# nrf52withamp.net
KiCad netlist of a schematic drawn in EAGLE
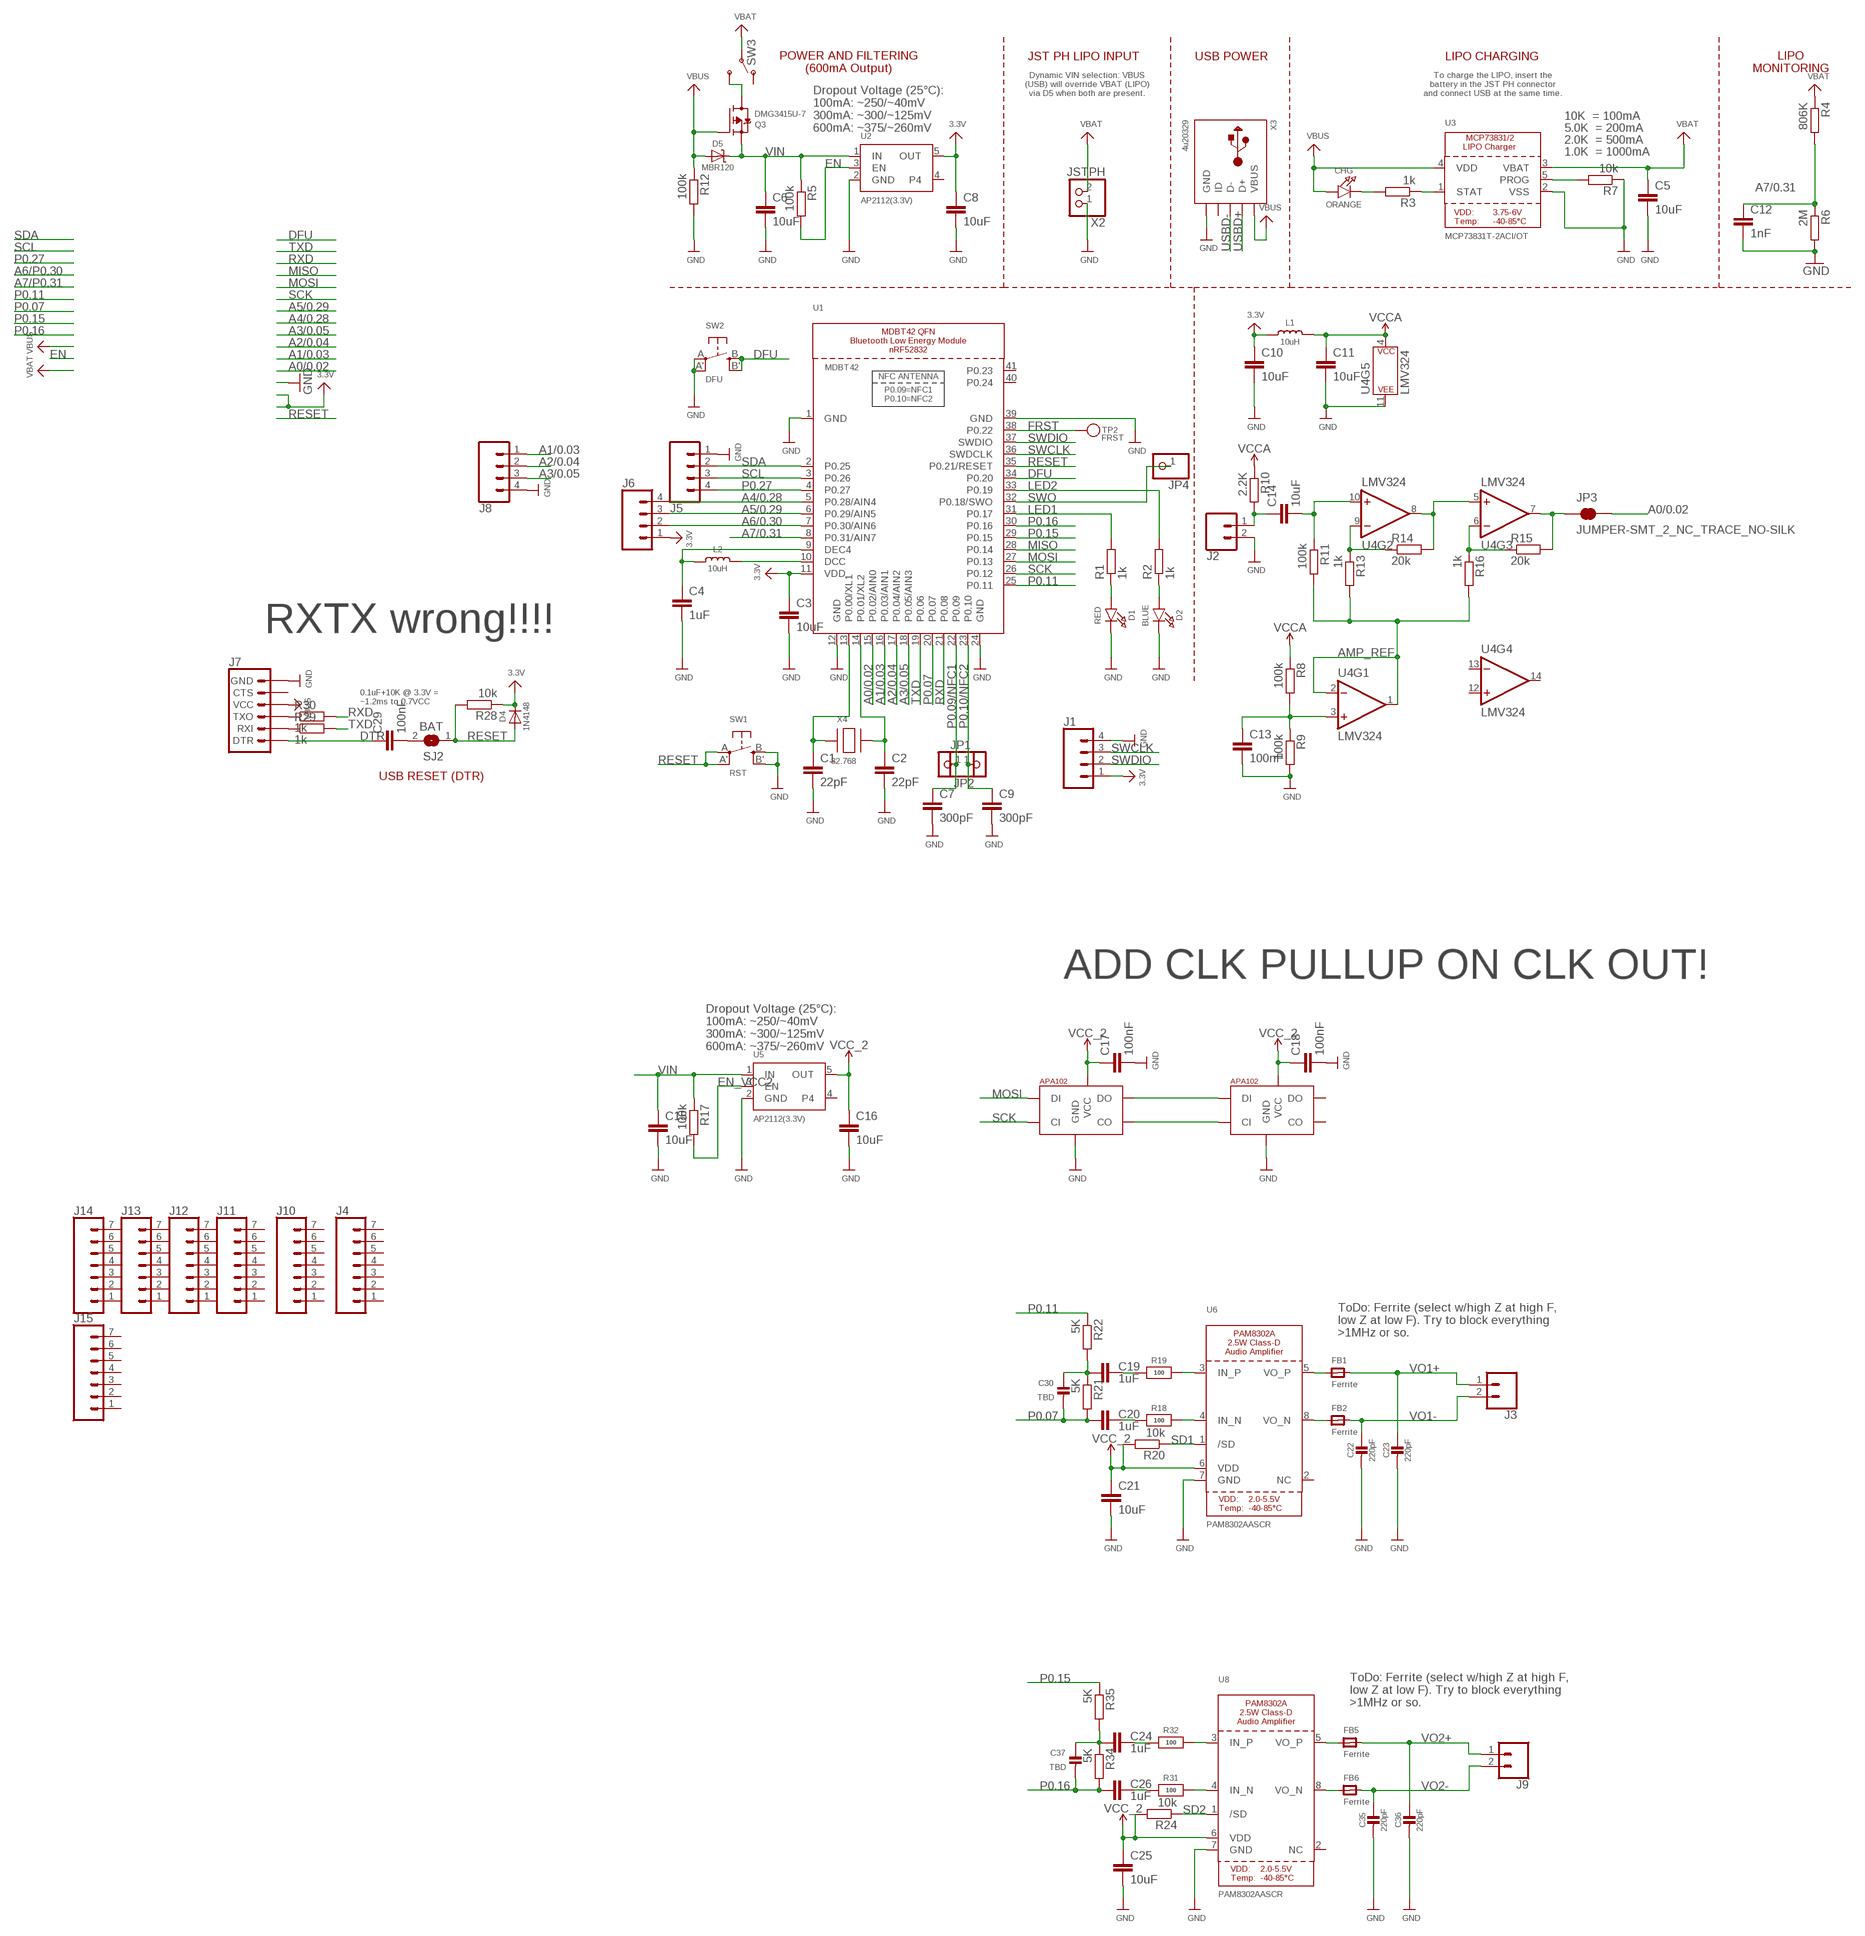
[diagram p0: schematic, sheet 1]

(export (version "E")
  (design (tool "Eeschema 10.0.6"))
  (components
    (comp (ref "C1")
      (value "22pF")
      (footprint "eagle-import:C0805")
      (libsource (lib "eagle-import") (part "C-EUC0805"))
    )
    (comp (ref "C2")
      (value "22pF")
      (footprint "eagle-import:C0805")
      (libsource (lib "eagle-import") (part "C-EUC0805"))
    )
    (comp (ref "C3")
      (value "10uF")
      (footprint "eagle-import:C0805")
      (libsource (lib "eagle-import") (part "C-EUC0805"))
    )
    (comp (ref "C4")
      (value "1uF")
      (footprint "eagle-import:C0805")
      (libsource (lib "eagle-import") (part "C-EUC0805"))
    )
    (comp (ref "C5")
      (value "10uF")
      (footprint "eagle-import:C0805")
      (libsource (lib "eagle-import") (part "C-EUC0805"))
    )
    (comp (ref "C6")
      (value "10uF")
      (footprint "eagle-import:C0805")
      (libsource (lib "eagle-import") (part "C-EUC0805"))
    )
    (comp (ref "C7")
      (value "300pF")
      (footprint "eagle-import:C0805")
      (libsource (lib "eagle-import") (part "C-EUC0805"))
    )
    (comp (ref "C8")
      (value "10uF")
      (footprint "eagle-import:C0805")
      (libsource (lib "eagle-import") (part "C-EUC0805"))
    )
    (comp (ref "C9")
      (value "300pF")
      (footprint "eagle-import:C0805")
      (libsource (lib "eagle-import") (part "C-EUC0805"))
    )
    (comp (ref "C10")
      (value "10uF")
      (footprint "eagle-import:C0805")
      (libsource (lib "eagle-import") (part "C-EUC0805"))
    )
    (comp (ref "C11")
      (value "10uF")
      (footprint "eagle-import:C0805")
      (libsource (lib "eagle-import") (part "C-EUC0805"))
    )
    (comp (ref "C12")
      (value "1nF")
      (footprint "eagle-import:C0805")
      (libsource (lib "eagle-import") (part "C-EUC0805"))
    )
    (comp (ref "C13")
      (value "100nF")
      (footprint "eagle-import:C0805")
      (libsource (lib "eagle-import") (part "C-EUC0805"))
    )
    (comp (ref "C14")
      (value "10uF")
      (footprint "eagle-import:C0805")
      (libsource (lib "eagle-import") (part "C-EUC0805"))
    )
    (comp (ref "C15")
      (value "10uF")
      (footprint "eagle-import:C0805")
      (libsource (lib "eagle-import") (part "C-EUC0805"))
    )
    (comp (ref "C16")
      (value "10uF")
      (footprint "eagle-import:C0805")
      (libsource (lib "eagle-import") (part "C-EUC0805"))
    )
    (comp (ref "C17")
      (value "100nF")
      (footprint "eagle-import:C0805")
      (libsource (lib "eagle-import") (part "C-EUC0805"))
    )
    (comp (ref "C18")
      (value "100nF")
      (footprint "eagle-import:C0805")
      (libsource (lib "eagle-import") (part "C-EUC0805"))
    )
    (comp (ref "C19")
      (value "1uF")
      (footprint "eagle-import:C0805")
      (libsource (lib "eagle-import") (part "C-EUC0805"))
    )
    (comp (ref "C20")
      (value "1uF")
      (footprint "eagle-import:C0805")
      (libsource (lib "eagle-import") (part "C-EUC0805"))
    )
    (comp (ref "C21")
      (value "10uF")
      (footprint "eagle-import:C0805")
      (libsource (lib "eagle-import") (part "C-EUC0805"))
    )
    (comp (ref "C22")
      (value "220pF")
      (footprint "eagle-import:0805-NO")
      (libsource (lib "eagle-import") (part "CAP_CERAMIC0805-NOOUTLINE"))
    )
    (comp (ref "C23")
      (value "220pF")
      (footprint "eagle-import:0805-NO")
      (libsource (lib "eagle-import") (part "CAP_CERAMIC0805-NOOUTLINE"))
    )
    (comp (ref "C24")
      (value "1uF")
      (footprint "eagle-import:C0805")
      (libsource (lib "eagle-import") (part "C-EUC0805"))
    )
    (comp (ref "C25")
      (value "10uF")
      (footprint "eagle-import:C0805")
      (libsource (lib "eagle-import") (part "C-EUC0805"))
    )
    (comp (ref "C26")
      (value "1uF")
      (footprint "eagle-import:C0805")
      (libsource (lib "eagle-import") (part "C-EUC0805"))
    )
    (comp (ref "C29")
      (value "100nF")
      (footprint "eagle-import:C0805")
      (libsource (lib "eagle-import") (part "C-EUC0805"))
    )
    (comp (ref "C30")
      (value "TBD")
      (footprint "eagle-import:0805-NO")
      (libsource (lib "eagle-import") (part "CAP_CERAMIC0805-NOOUTLINE"))
    )
    (comp (ref "C35")
      (value "220pF")
      (footprint "eagle-import:0805-NO")
      (libsource (lib "eagle-import") (part "CAP_CERAMIC0805-NOOUTLINE"))
    )
    (comp (ref "C36")
      (value "220pF")
      (footprint "eagle-import:0805-NO")
      (libsource (lib "eagle-import") (part "CAP_CERAMIC0805-NOOUTLINE"))
    )
    (comp (ref "C37")
      (value "TBD")
      (footprint "eagle-import:0805-NO")
      (libsource (lib "eagle-import") (part "CAP_CERAMIC0805-NOOUTLINE"))
    )
    (comp (ref "CHG")
      (value "ORANGE")
      (footprint "eagle-import:CHIPLED_0805_NOOUTLINE")
      (libsource (lib "eagle-import") (part "LED0805_NOOUTLINE"))
    )
    (comp (ref "D1")
      (value "RED")
      (footprint "eagle-import:CHIPLED_0805_NOOUTLINE")
      (libsource (lib "eagle-import") (part "LED0805_NOOUTLINE"))
    )
    (comp (ref "D2")
      (value "BLUE")
      (footprint "eagle-import:CHIPLED_0805_NOOUTLINE")
      (libsource (lib "eagle-import") (part "LED0805_NOOUTLINE"))
    )
    (comp (ref "D4")
      (value "1N4148")
      (footprint "eagle-import:SOD-323")
      (libsource (lib "eagle-import") (part "DIODESOD-323"))
    )
    (comp (ref "D5")
      (value "MBR120")
      (footprint "eagle-import:SOD-123")
      (libsource (lib "eagle-import") (part "DIODE-SCHOTTKYSOD-123"))
    )
    (comp (ref "FB1")
      (value "Ferrite")
      (footprint "eagle-import:_0805")
      (libsource (lib "eagle-import") (part "FERRITE_0805"))
    )
    (comp (ref "FB2")
      (value "Ferrite")
      (footprint "eagle-import:_0805")
      (libsource (lib "eagle-import") (part "FERRITE_0805"))
    )
    (comp (ref "FB5")
      (value "Ferrite")
      (footprint "eagle-import:_0805")
      (libsource (lib "eagle-import") (part "FERRITE_0805"))
    )
    (comp (ref "FB6")
      (value "Ferrite")
      (footprint "eagle-import:_0805")
      (libsource (lib "eagle-import") (part "FERRITE_0805"))
    )
    (comp (ref "J1")
      (value "CONN_04SMD")
      (footprint "eagle-import:1X04_SMD_RA_MALE")
      (libsource (lib "eagle-import") (part "CONN_04SMD"))
    )
    (comp (ref "J2")
      (value "CONN_02")
      (footprint "eagle-import:1X02")
      (libsource (lib "eagle-import") (part "CONN_02"))
    )
    (comp (ref "J3")
      (value "CONN_02")
      (footprint "eagle-import:1X02")
      (libsource (lib "eagle-import") (part "CONN_02"))
    )
    (comp (ref "J4")
      (value "CONN_07")
      (footprint "eagle-import:1X07")
      (libsource (lib "eagle-import") (part "CONN_07"))
    )
    (comp (ref "J5")
      (value "CONN_041.27MM")
      (footprint "eagle-import:1X04_1.27MM")
      (libsource (lib "eagle-import") (part "CONN_041.27MM"))
    )
    (comp (ref "J6")
      (value "CONN_041.27MM")
      (footprint "eagle-import:1X04_1.27MM")
      (libsource (lib "eagle-import") (part "CONN_041.27MM"))
    )
    (comp (ref "J7")
      (value "6_PIN_SERIAL_TARGETRA_SMT")
      (footprint "eagle-import:6_PIN_SERIAL_TARGET_SIDE_RA_SMT")
      (libsource (lib "eagle-import") (part "6_PIN_SERIAL_TARGETRA_SMT"))
    )
    (comp (ref "J8")
      (value "CONN_041.27MM")
      (footprint "eagle-import:1X04_1.27MM")
      (libsource (lib "eagle-import") (part "CONN_041.27MM"))
    )
    (comp (ref "J9")
      (value "CONN_02")
      (footprint "eagle-import:1X02")
      (libsource (lib "eagle-import") (part "CONN_02"))
    )
    (comp (ref "J10")
      (value "CONN_07")
      (footprint "eagle-import:1X07")
      (libsource (lib "eagle-import") (part "CONN_07"))
    )
    (comp (ref "J11")
      (value "CONN_07")
      (footprint "eagle-import:1X07")
      (libsource (lib "eagle-import") (part "CONN_07"))
    )
    (comp (ref "J12")
      (value "CONN_07")
      (footprint "eagle-import:1X07")
      (libsource (lib "eagle-import") (part "CONN_07"))
    )
    (comp (ref "J13")
      (value "CONN_07")
      (footprint "eagle-import:1X07")
      (libsource (lib "eagle-import") (part "CONN_07"))
    )
    (comp (ref "J14")
      (value "CONN_07")
      (footprint "eagle-import:1X07")
      (libsource (lib "eagle-import") (part "CONN_07"))
    )
    (comp (ref "J15")
      (value "CONN_07")
      (footprint "eagle-import:1X07")
      (libsource (lib "eagle-import") (part "CONN_07"))
    )
    (comp (ref "JP1")
      (value "HEADER-1X12MM")
      (footprint "eagle-import:1X01_2MM")
      (libsource (lib "eagle-import") (part "HEADER-1X12MM"))
    )
    (comp (ref "JP2")
      (value "HEADER-1X12MM")
      (footprint "eagle-import:1X01_2MM")
      (libsource (lib "eagle-import") (part "HEADER-1X12MM"))
    )
    (comp (ref "JP3")
      (value "JUMPER-SMT_2_NC_TRACE_NO-SILK")
      (footprint "eagle-import:SMT-JUMPER_2_NC_TRACE_NO-SILK")
      (libsource (lib "eagle-import") (part "JUMPER-SMT_2_NC_TRACE_NO-SILK"))
    )
    (comp (ref "JP4")
      (value "HEADER-1X12MM")
      (footprint "eagle-import:1X01_2MM")
      (libsource (lib "eagle-import") (part "HEADER-1X12MM"))
    )
    (comp (ref "L1")
      (value "10uH")
      (footprint "eagle-import:0805-NO@1")
      (libsource (lib "eagle-import") (part "INDUCTOR0805-NO"))
    )
    (comp (ref "L2")
      (value "10uH")
      (footprint "eagle-import:0805-NO@1")
      (libsource (lib "eagle-import") (part "INDUCTOR0805-NO"))
    )
    (comp (ref "Q3")
      (value "DMG3415U-7")
      (footprint "eagle-import:SOT23-R")
      (libsource (lib "eagle-import") (part "MOSFET-P"))
    )
    (comp (ref "R1")
      (value "1k")
      (footprint "eagle-import:R0805")
      (libsource (lib "eagle-import") (part "R-EU_R0805"))
    )
    (comp (ref "R2")
      (value "1k")
      (footprint "eagle-import:R0805")
      (libsource (lib "eagle-import") (part "R-EU_R0805"))
    )
    (comp (ref "R3")
      (value "1k")
      (footprint "eagle-import:R0805")
      (libsource (lib "eagle-import") (part "R-EU_R0805"))
    )
    (comp (ref "R4")
      (value "806K")
      (footprint "eagle-import:R0805")
      (libsource (lib "eagle-import") (part "R-EU_R0805"))
    )
    (comp (ref "R5")
      (value "100k")
      (footprint "eagle-import:R0805")
      (libsource (lib "eagle-import") (part "R-EU_R0805"))
    )
    (comp (ref "R6")
      (value "2M")
      (footprint "eagle-import:R0805")
      (libsource (lib "eagle-import") (part "R-EU_R0805"))
    )
    (comp (ref "R7")
      (value "10k")
      (footprint "eagle-import:R0805")
      (libsource (lib "eagle-import") (part "R-EU_R0805"))
    )
    (comp (ref "R8")
      (value "100k")
      (footprint "eagle-import:R0805")
      (libsource (lib "eagle-import") (part "R-EU_R0805"))
    )
    (comp (ref "R9")
      (value "100k")
      (footprint "eagle-import:R0805")
      (libsource (lib "eagle-import") (part "R-EU_R0805"))
    )
    (comp (ref "R10")
      (value "2.2K")
      (footprint "eagle-import:R0805")
      (libsource (lib "eagle-import") (part "R-EU_R0805"))
    )
    (comp (ref "R11")
      (value "100k")
      (footprint "eagle-import:R0805")
      (libsource (lib "eagle-import") (part "R-EU_R0805"))
    )
    (comp (ref "R12")
      (value "100k")
      (footprint "eagle-import:R0805")
      (libsource (lib "eagle-import") (part "R-EU_R0805"))
    )
    (comp (ref "R13")
      (value "1k")
      (footprint "eagle-import:R0805")
      (libsource (lib "eagle-import") (part "R-EU_R0805"))
    )
    (comp (ref "R14")
      (value "20k")
      (footprint "eagle-import:R0805")
      (libsource (lib "eagle-import") (part "R-EU_R0805"))
    )
    (comp (ref "R15")
      (value "20k")
      (footprint "eagle-import:R0805")
      (libsource (lib "eagle-import") (part "R-EU_R0805"))
    )
    (comp (ref "R16")
      (value "1k")
      (footprint "eagle-import:R0805")
      (libsource (lib "eagle-import") (part "R-EU_R0805"))
    )
    (comp (ref "R17")
      (value "100k")
      (footprint "eagle-import:R0805")
      (libsource (lib "eagle-import") (part "R-EU_R0805"))
    )
    (comp (ref "R18")
      (value "100")
      (footprint "eagle-import:0805-NO")
      (libsource (lib "eagle-import") (part "RESISTOR0805_NOOUTLINE"))
    )
    (comp (ref "R19")
      (value "100")
      (footprint "eagle-import:0805-NO")
      (libsource (lib "eagle-import") (part "RESISTOR0805_NOOUTLINE"))
    )
    (comp (ref "R20")
      (value "10k")
      (footprint "eagle-import:R0805")
      (libsource (lib "eagle-import") (part "R-EU_R0805"))
    )
    (comp (ref "R21")
      (value "5K")
      (footprint "eagle-import:R0805")
      (libsource (lib "eagle-import") (part "R-EU_R0805"))
    )
    (comp (ref "R22")
      (value "5K")
      (footprint "eagle-import:R0805")
      (libsource (lib "eagle-import") (part "R-EU_R0805"))
    )
    (comp (ref "R24")
      (value "10k")
      (footprint "eagle-import:R0805")
      (libsource (lib "eagle-import") (part "R-EU_R0805"))
    )
    (comp (ref "R28")
      (value "10k")
      (footprint "eagle-import:R0805")
      (libsource (lib "eagle-import") (part "R-EU_R0805"))
    )
    (comp (ref "R29")
      (value "1k")
      (footprint "eagle-import:R0805")
      (libsource (lib "eagle-import") (part "R-EU_R0805"))
    )
    (comp (ref "R30")
      (value "1k")
      (footprint "eagle-import:R0805")
      (libsource (lib "eagle-import") (part "R-EU_R0805"))
    )
    (comp (ref "R31")
      (value "100")
      (footprint "eagle-import:0805-NO")
      (libsource (lib "eagle-import") (part "RESISTOR0805_NOOUTLINE"))
    )
    (comp (ref "R32")
      (value "100")
      (footprint "eagle-import:0805-NO")
      (libsource (lib "eagle-import") (part "RESISTOR0805_NOOUTLINE"))
    )
    (comp (ref "R34")
      (value "5K")
      (footprint "eagle-import:R0805")
      (libsource (lib "eagle-import") (part "R-EU_R0805"))
    )
    (comp (ref "R35")
      (value "5K")
      (footprint "eagle-import:R0805")
      (libsource (lib "eagle-import") (part "R-EU_R0805"))
    )
    (comp (ref "SJ2")
      (value "BAT")
      (footprint "eagle-import:SOLDERJUMPER_CLOSEDWIRE")
      (libsource (lib "eagle-import") (part "SOLDERJUMPERCLOSED"))
    )
    (comp (ref "SW1")
      (value "RST")
      (footprint "eagle-import:BTN_KMR2_4.6X2.8")
      (libsource (lib "eagle-import") (part "SWITCH_TACT_SMT4.6X2.8"))
    )
    (comp (ref "SW2")
      (value "DFU")
      (footprint "eagle-import:BTN_KMR2_4.6X2.8")
      (libsource (lib "eagle-import") (part "SWITCH_TACT_SMT4.6X2.8"))
    )
    (comp (ref "SW3")
      (value "SWITCH_SPDT")
      (footprint "eagle-import:KPS-1290")
      (libsource (lib "eagle-import") (part "SWITCH_SPDT"))
    )
    (comp (ref "TP2")
      (value "FRST")
      (footprint "eagle-import:PAD-1.5X2.0")
      (libsource (lib "eagle-import") (part "TESTPOINT1.5X2.0MM_NOCREAM"))
    )
    (comp (ref "U$45")
      (value "APA1022020")
      (footprint "eagle-import:APA102_2020")
      (libsource (lib "eagle-import") (part "APA1022020"))
    )
    (comp (ref "U$51")
      (value "APA1022020")
      (footprint "eagle-import:APA102_2020")
      (libsource (lib "eagle-import") (part "APA1022020"))
    )
    (comp (ref "U1")
      (value "MDBT42")
      (footprint "eagle-import:BLE_MODULE_RAYTAC_MDBT42")
      (libsource (lib "eagle-import") (part "NRF52832_MODULE_MDBT42"))
    )
    (comp (ref "U2")
      (value "AP2112(3.3V)")
      (footprint "eagle-import:SOT23-5")
      (libsource (lib "eagle-import") (part "VREG_SOT23-5"))
    )
    (comp (ref "U3")
      (value "MCP73831T-2ACI/OT")
      (footprint "eagle-import:SOT23-5")
      (libsource (lib "eagle-import") (part "MCP73831/2"))
    )
    (comp (ref "U4")
      (value "LMV324")
      (footprint "eagle-import:SO14")
      (fields (field (name "LCSC") "C7974"))
      (libsource (lib "eagle-import") (part "LMV324"))
    )
    (comp (ref "U5")
      (value "AP2112(3.3V)")
      (footprint "eagle-import:SOT23-5")
      (libsource (lib "eagle-import") (part "VREG_SOT23-5"))
    )
    (comp (ref "U6")
      (value "PAM8302AASCR")
      (footprint "eagle-import:MSOP8_0.65MM")
      (libsource (lib "eagle-import") (part "AUDIOAMP_PAM8302A"))
    )
    (comp (ref "U8")
      (value "PAM8302AASCR")
      (footprint "eagle-import:MSOP8_0.65MM")
      (libsource (lib "eagle-import") (part "AUDIOAMP_PAM8302A"))
    )
    (comp (ref "X2")
      (value "JSTPH")
      (footprint "eagle-import:JSTPH2")
      (libsource (lib "eagle-import") (part "CON_JST_PH_2PIN"))
    )
    (comp (ref "X3")
      (value "4u20329")
      (footprint "eagle-import:4UCONN_20329_V2")
      (libsource (lib "eagle-import") (part "USB_MICRO_20329_V2"))
    )
    (comp (ref "X4")
      (value "32.768")
      (footprint "eagle-import:XTAL3215")
      (libsource (lib "eagle-import") (part "XTAL-3.2X1.5"))
    )
  )
  (nets
    (net (code "1") (name "/A0{slash}0.02") (class "Default")
      (node (ref "JP3") (pin "2") (pinfunction "2_2") (pintype "passive"))
      (node (ref "U1") (pin "15") (pinfunction "P0.02/AIN0_15") (pintype "bidirectional"))
    )
    (net (code "2") (name "/A1{slash}0.03") (class "Default")
      (node (ref "J8") (pin "1") (pinfunction "1_1") (pintype "passive"))
      (node (ref "U1") (pin "16") (pinfunction "P0.03/AIN1_16") (pintype "bidirectional"))
    )
    (net (code "3") (name "/A2{slash}0.04") (class "Default")
      (node (ref "J8") (pin "2") (pinfunction "2_2") (pintype "passive"))
      (node (ref "U1") (pin "17") (pinfunction "P0.04/AIN2_17") (pintype "bidirectional"))
    )
    (net (code "4") (name "/A3{slash}0.05") (class "Default")
      (node (ref "J8") (pin "3") (pinfunction "3_3") (pintype "passive"))
      (node (ref "U1") (pin "18") (pinfunction "P0.05/AIN3_18") (pintype "bidirectional"))
    )
    (net (code "5") (name "/A4{slash}0.28") (class "Default")
      (node (ref "J6") (pin "4") (pinfunction "4_4") (pintype "passive"))
      (node (ref "U1") (pin "5") (pinfunction "P0.28/AIN4_5") (pintype "bidirectional"))
    )
    (net (code "6") (name "/A5{slash}0.29") (class "Default")
      (node (ref "J6") (pin "3") (pinfunction "3_3") (pintype "passive"))
      (node (ref "U1") (pin "6") (pinfunction "P0.29/AIN5_6") (pintype "bidirectional"))
    )
    (net (code "7") (name "/A6{slash}0.30") (class "Default")
      (node (ref "J6") (pin "2") (pinfunction "2_2") (pintype "passive"))
      (node (ref "U1") (pin "7") (pinfunction "P0.30/AIN6_7") (pintype "bidirectional"))
    )
    (net (code "9") (name "/A7{slash}0.31") (class "Default")
      (node (ref "C12") (pin "1") (pinfunction "1_1") (pintype "passive"))
      (node (ref "R4") (pin "2") (pinfunction "2_2") (pintype "passive"))
      (node (ref "R6") (pin "1") (pinfunction "1_1") (pintype "passive"))
      (node (ref "U1") (pin "8") (pinfunction "P0.31/AIN7_8") (pintype "bidirectional"))
    )
    (net (code "11") (name "/AMP_REF") (class "Default")
      (node (ref "R11") (pin "2") (pinfunction "2_2") (pintype "passive"))
      (node (ref "R13") (pin "2") (pinfunction "2_2") (pintype "passive"))
      (node (ref "R16") (pin "2") (pinfunction "2_2") (pintype "passive"))
      (node (ref "U4") (pin "1") (pinfunction "OUT_1") (pintype "output"))
      (node (ref "U4") (pin "2") (pinfunction "-IN_2") (pintype "input"))
    )
    (net (code "12") (name "/DFU") (class "Default")
      (node (ref "SW2") (pin "B") (pinfunction "S_B") (pintype "passive"))
      (node (ref "SW2") (pin "B'") (pinfunction "S1_B'") (pintype "passive"))
      (node (ref "U1") (pin "34") (pinfunction "P0.20_34") (pintype "bidirectional"))
    )
    (net (code "13") (name "/DTR") (class "Default")
      (node (ref "C29") (pin "1") (pinfunction "1_1") (pintype "passive"))
      (node (ref "J7") (pin "1") (pinfunction "DTR_1") (pintype "passive"))
    )
    (net (code "14") (name "/EN") (class "Default")
      (node (ref "R5") (pin "2") (pinfunction "2_2") (pintype "passive"))
      (node (ref "U2") (pin "3") (pinfunction "EN_3") (pintype "input"))
    )
    (net (code "15") (name "/EN_VCC2") (class "Default")
      (node (ref "R17") (pin "2") (pinfunction "2_2") (pintype "passive"))
      (node (ref "U5") (pin "3") (pinfunction "EN_3") (pintype "input"))
    )
    (net (code "16") (name "/FRST") (class "Default")
      (node (ref "TP2") (pin "P$1") (pinfunction "P$1_P$1") (pintype "bidirectional"))
      (node (ref "U1") (pin "38") (pinfunction "P0.22_38") (pintype "bidirectional"))
    )
    (net (code "17") (name "/LED1") (class "Default")
      (node (ref "R1") (pin "2") (pinfunction "2_2") (pintype "passive"))
      (node (ref "U1") (pin "31") (pinfunction "P0.17_31") (pintype "bidirectional"))
    )
    (net (code "18") (name "/LED2") (class "Default")
      (node (ref "R2") (pin "2") (pinfunction "2_2") (pintype "passive"))
      (node (ref "U1") (pin "33") (pinfunction "P0.19_33") (pintype "bidirectional"))
    )
    (net (code "19") (name "/MISO") (class "Default")
      (node (ref "U1") (pin "28") (pinfunction "P0.14_28") (pintype "bidirectional"))
    )
    (net (code "20") (name "/MOSI") (class "Default")
      (node (ref "U$45") (pin "D_IN") (pinfunction "DI_D_IN") (pintype "bidirectional"))
      (node (ref "U1") (pin "27") (pinfunction "P0.13_27") (pintype "bidirectional"))
    )
    (net (code "21") (name "/P0.07") (class "Default")
      (node (ref "C20") (pin "1") (pinfunction "1_1") (pintype "passive"))
      (node (ref "C30") (pin "2") (pinfunction "2_2") (pintype "passive"))
      (node (ref "R21") (pin "2") (pinfunction "2_2") (pintype "passive"))
      (node (ref "U1") (pin "20") (pinfunction "P0.07_20") (pintype "bidirectional"))
    )
    (net (code "22") (name "/P0.09{slash}NFC1") (class "Default")
      (node (ref "C7") (pin "1") (pinfunction "1_1") (pintype "passive"))
      (node (ref "JP2") (pin "1") (pinfunction "1_1") (pintype "passive"))
      (node (ref "U1") (pin "22") (pinfunction "P0.09_22") (pintype "bidirectional"))
    )
    (net (code "23") (name "/P0.10{slash}NFC2") (class "Default")
      (node (ref "C9") (pin "1") (pinfunction "1_1") (pintype "passive"))
      (node (ref "JP1") (pin "1") (pinfunction "1_1") (pintype "passive"))
      (node (ref "U1") (pin "23") (pinfunction "P0.10_23") (pintype "bidirectional"))
    )
    (net (code "24") (name "/P0.11") (class "Default")
      (node (ref "R22") (pin "1") (pinfunction "1_1") (pintype "passive"))
      (node (ref "U1") (pin "25") (pinfunction "P0.11_25") (pintype "bidirectional"))
    )
    (net (code "25") (name "/P0.15") (class "Default")
      (node (ref "R35") (pin "1") (pinfunction "1_1") (pintype "passive"))
      (node (ref "U1") (pin "29") (pinfunction "P0.15_29") (pintype "bidirectional"))
    )
    (net (code "26") (name "/P0.16") (class "Default")
      (node (ref "C26") (pin "1") (pinfunction "1_1") (pintype "passive"))
      (node (ref "C37") (pin "2") (pinfunction "2_2") (pintype "passive"))
      (node (ref "R34") (pin "2") (pinfunction "2_2") (pintype "passive"))
      (node (ref "U1") (pin "30") (pinfunction "P0.16_30") (pintype "bidirectional"))
    )
    (net (code "27") (name "/P0.27") (class "Default")
      (node (ref "J5") (pin "4") (pinfunction "4_4") (pintype "passive"))
      (node (ref "U1") (pin "4") (pinfunction "P0.27_4") (pintype "bidirectional"))
    )
    (net (code "28") (name "/RESET") (class "Default")
      (node (ref "D4") (pin "A") (pinfunction "A_A") (pintype "passive"))
      (node (ref "R28") (pin "2") (pinfunction "2_2") (pintype "passive"))
      (node (ref "SJ2") (pin "1") (pinfunction "1_1") (pintype "passive"))
      (node (ref "SW1") (pin "A") (pinfunction "P_A") (pintype "passive"))
      (node (ref "SW1") (pin "A'") (pinfunction "P1_A'") (pintype "passive"))
      (node (ref "U1") (pin "35") (pinfunction "P0.21/RESET_35") (pintype "bidirectional"))
    )
    (net (code "29") (name "/RXD") (class "Default")
      (node (ref "R30") (pin "2") (pinfunction "2_2") (pintype "passive"))
      (node (ref "U1") (pin "21") (pinfunction "P0.08_21") (pintype "bidirectional"))
    )
    (net (code "30") (name "/SCK") (class "Default")
      (node (ref "U$45") (pin "C_IN") (pinfunction "CI_C_IN") (pintype "bidirectional"))
      (node (ref "U1") (pin "26") (pinfunction "P0.12_26") (pintype "bidirectional"))
    )
    (net (code "31") (name "/SCL") (class "Default")
      (node (ref "J5") (pin "3") (pinfunction "3_3") (pintype "passive"))
      (node (ref "U1") (pin "3") (pinfunction "P0.26_3") (pintype "bidirectional"))
    )
    (net (code "32") (name "/SD1") (class "Default")
      (node (ref "R20") (pin "1") (pinfunction "1_1") (pintype "passive"))
      (node (ref "U6") (pin "1") (pinfunction "/SD_1") (pintype "input"))
    )
    (net (code "33") (name "/SD2") (class "Default")
      (node (ref "R24") (pin "1") (pinfunction "1_1") (pintype "passive"))
      (node (ref "U8") (pin "1") (pinfunction "/SD_1") (pintype "input"))
    )
    (net (code "34") (name "/SDA") (class "Default")
      (node (ref "J5") (pin "2") (pinfunction "2_2") (pintype "passive"))
      (node (ref "U1") (pin "2") (pinfunction "P0.25_2") (pintype "bidirectional"))
    )
    (net (code "35") (name "/SWCLK") (class "Default")
      (node (ref "J1") (pin "3") (pinfunction "3_3") (pintype "passive"))
      (node (ref "U1") (pin "36") (pinfunction "SWDCLK_36") (pintype "bidirectional"))
    )
    (net (code "36") (name "/SWDIO") (class "Default")
      (node (ref "J1") (pin "2") (pinfunction "2_2") (pintype "passive"))
      (node (ref "U1") (pin "37") (pinfunction "SWDIO_37") (pintype "bidirectional"))
    )
    (net (code "37") (name "/SWO") (class "Default")
      (node (ref "JP4") (pin "1") (pinfunction "1_1") (pintype "passive"))
      (node (ref "U1") (pin "32") (pinfunction "P0.18/SWO_32") (pintype "bidirectional"))
    )
    (net (code "38") (name "/TXD") (class "Default")
      (node (ref "R29") (pin "2") (pinfunction "2_2") (pintype "passive"))
      (node (ref "U1") (pin "19") (pinfunction "P0.06_19") (pintype "bidirectional"))
    )
    (net (code "39") (name "/USBD+") (class "Default")
      (node (ref "X3") (pin "D+") (pinfunction "D+_D+") (pintype "bidirectional"))
    )
    (net (code "40") (name "/USBD-") (class "Default")
      (node (ref "X3") (pin "D-") (pinfunction "D-_D-") (pintype "bidirectional"))
    )
    (net (code "41") (name "/VIN") (class "Default")
      (node (ref "C15") (pin "1") (pinfunction "1_1") (pintype "passive"))
      (node (ref "C6") (pin "1") (pinfunction "1_1") (pintype "passive"))
      (node (ref "D5") (pin "C") (pinfunction "C_C") (pintype "passive"))
      (node (ref "Q3") (pin "2") (pinfunction "S_2") (pintype "passive"))
      (node (ref "R17") (pin "1") (pinfunction "1_1") (pintype "passive"))
      (node (ref "R5") (pin "1") (pinfunction "1_1") (pintype "passive"))
      (node (ref "U2") (pin "1") (pinfunction "IN_1") (pintype "power_in"))
      (node (ref "U5") (pin "1") (pinfunction "IN_1") (pintype "power_in"))
    )
    (net (code "42") (name "/VO1+") (class "Default")
      (node (ref "C23") (pin "1") (pinfunction "1_1") (pintype "passive"))
      (node (ref "FB1") (pin "2") (pinfunction "P$2_2") (pintype "passive"))
      (node (ref "J3") (pin "1") (pinfunction "1_1") (pintype "passive"))
    )
    (net (code "43") (name "/VO1-") (class "Default")
      (node (ref "C22") (pin "1") (pinfunction "1_1") (pintype "passive"))
      (node (ref "FB2") (pin "2") (pinfunction "P$2_2") (pintype "passive"))
      (node (ref "J3") (pin "2") (pinfunction "2_2") (pintype "passive"))
    )
    (net (code "44") (name "/VO2+") (class "Default")
      (node (ref "C36") (pin "1") (pinfunction "1_1") (pintype "passive"))
      (node (ref "FB5") (pin "2") (pinfunction "P$2_2") (pintype "passive"))
      (node (ref "J9") (pin "1") (pinfunction "1_1") (pintype "passive"))
    )
    (net (code "45") (name "/VO2-") (class "Default")
      (node (ref "C35") (pin "1") (pinfunction "1_1") (pintype "passive"))
      (node (ref "FB6") (pin "2") (pinfunction "P$2_2") (pintype "passive"))
      (node (ref "J9") (pin "2") (pinfunction "2_2") (pintype "passive"))
    )
    (net (code "46") (name "3.3V") (class "Default")
      (node (ref "C10") (pin "1") (pinfunction "1_1") (pintype "passive"))
      (node (ref "C3") (pin "1") (pinfunction "1_1") (pintype "passive"))
      (node (ref "C8") (pin "1") (pinfunction "1_1") (pintype "passive"))
      (node (ref "D4") (pin "C") (pinfunction "C_C") (pintype "passive"))
      (node (ref "J1") (pin "1") (pinfunction "1_1") (pintype "passive"))
      (node (ref "J6") (pin "1") (pinfunction "1_1") (pintype "passive"))
      (node (ref "L1") (pin "1") (pinfunction "1_1") (pintype "passive"))
      (node (ref "R28") (pin "1") (pinfunction "1_1") (pintype "passive"))
      (node (ref "U1") (pin "11") (pinfunction "VDD_11") (pintype "bidirectional"))
      (node (ref "U2") (pin "5") (pinfunction "OUT_5") (pintype "power_in"))
    )
    (net (code "47") (name "GND") (class "Default")
      (node (ref "C1") (pin "2") (pinfunction "2_2") (pintype "passive"))
      (node (ref "C10") (pin "2") (pinfunction "2_2") (pintype "passive"))
      (node (ref "C11") (pin "2") (pinfunction "2_2") (pintype "passive"))
      (node (ref "C12") (pin "2") (pinfunction "2_2") (pintype "passive"))
      (node (ref "C13") (pin "2") (pinfunction "2_2") (pintype "passive"))
      (node (ref "C15") (pin "2") (pinfunction "2_2") (pintype "passive"))
      (node (ref "C16") (pin "2") (pinfunction "2_2") (pintype "passive"))
      (node (ref "C17") (pin "2") (pinfunction "2_2") (pintype "passive"))
      (node (ref "C18") (pin "2") (pinfunction "2_2") (pintype "passive"))
      (node (ref "C2") (pin "2") (pinfunction "2_2") (pintype "passive"))
      (node (ref "C21") (pin "2") (pinfunction "2_2") (pintype "passive"))
      (node (ref "C22") (pin "2") (pinfunction "2_2") (pintype "passive"))
      (node (ref "C23") (pin "2") (pinfunction "2_2") (pintype "passive"))
      (node (ref "C25") (pin "2") (pinfunction "2_2") (pintype "passive"))
      (node (ref "C3") (pin "2") (pinfunction "2_2") (pintype "passive"))
      (node (ref "C35") (pin "2") (pinfunction "2_2") (pintype "passive"))
      (node (ref "C36") (pin "2") (pinfunction "2_2") (pintype "passive"))
      (node (ref "C4") (pin "2") (pinfunction "2_2") (pintype "passive"))
      (node (ref "C5") (pin "2") (pinfunction "2_2") (pintype "passive"))
      (node (ref "C6") (pin "2") (pinfunction "2_2") (pintype "passive"))
      (node (ref "C7") (pin "2") (pinfunction "2_2") (pintype "passive"))
      (node (ref "C8") (pin "2") (pinfunction "2_2") (pintype "passive"))
      (node (ref "C9") (pin "2") (pinfunction "2_2") (pintype "passive"))
      (node (ref "D1") (pin "C") (pinfunction "C_C") (pintype "passive"))
      (node (ref "D2") (pin "C") (pinfunction "C_C") (pintype "passive"))
      (node (ref "J1") (pin "4") (pinfunction "4_4") (pintype "passive"))
      (node (ref "J2") (pin "2") (pinfunction "2_2") (pintype "passive"))
      (node (ref "J5") (pin "1") (pinfunction "1_1") (pintype "passive"))
      (node (ref "J7") (pin "6") (pinfunction "GND_6") (pintype "passive"))
      (node (ref "J8") (pin "4") (pinfunction "4_4") (pintype "passive"))
      (node (ref "R12") (pin "2") (pinfunction "2_2") (pintype "passive"))
      (node (ref "R6") (pin "2") (pinfunction "2_2") (pintype "passive"))
      (node (ref "R7") (pin "1") (pinfunction "1_1") (pintype "passive"))
      (node (ref "R9") (pin "2") (pinfunction "2_2") (pintype "passive"))
      (node (ref "SW1") (pin "B") (pinfunction "S_B") (pintype "passive"))
      (node (ref "SW1") (pin "B'") (pinfunction "S1_B'") (pintype "passive"))
      (node (ref "SW2") (pin "A") (pinfunction "P_A") (pintype "passive"))
      (node (ref "SW2") (pin "A'") (pinfunction "P1_A'") (pintype "passive"))
      (node (ref "U$45") (pin "GND") (pinfunction "GND_GND") (pintype "bidirectional"))
      (node (ref "U$51") (pin "GND") (pinfunction "GND_GND") (pintype "bidirectional"))
      (node (ref "U1") (pin "1") (pinfunction "GND_1") (pintype "bidirectional"))
      (node (ref "U1") (pin "12") (pinfunction "GND_12") (pintype "bidirectional"))
      (node (ref "U1") (pin "24") (pinfunction "GND_24") (pintype "bidirectional"))
      (node (ref "U1") (pin "39") (pinfunction "GND_39") (pintype "bidirectional"))
      (node (ref "U2") (pin "2") (pinfunction "GND_2") (pintype "power_in"))
      (node (ref "U3") (pin "2") (pinfunction "VSS_2") (pintype "power_in"))
      (node (ref "U4") (pin "11") (pinfunction "P$V-_11") (pintype "bidirectional"))
      (node (ref "U5") (pin "2") (pinfunction "GND_2") (pintype "power_in"))
      (node (ref "U6") (pin "7") (pinfunction "GND_7") (pintype "power_in"))
      (node (ref "U8") (pin "7") (pinfunction "GND_7") (pintype "power_in"))
      (node (ref "X2") (pin "1") (pinfunction "1_1") (pintype "passive"))
      (node (ref "X3") (pin "BASE@1") (pinfunction "GND_BASE@1") (pintype "power_in"))
      (node (ref "X3") (pin "BASE@2") (pinfunction "GND_BASE@2") (pintype "power_in"))
      (node (ref "X3") (pin "GND") (pinfunction "GND_GND") (pintype "power_in"))
      (node (ref "X3") (pin "SPRT@1") (pinfunction "GND_SPRT@1") (pintype "power_in"))
      (node (ref "X3") (pin "SPRT@2") (pinfunction "GND_SPRT@2") (pintype "power_in"))
      (node (ref "X3") (pin "SPRT@3") (pinfunction "GND_SPRT@3") (pintype "power_in"))
      (node (ref "X3") (pin "SPRT@4") (pinfunction "GND_SPRT@4") (pintype "power_in"))
    )
    (net (code "48") (name "Net-(C14-Pad1)") (class "Default")
      (node (ref "C14") (pin "1") (pinfunction "1_1") (pintype "passive"))
      (node (ref "J2") (pin "1") (pinfunction "1_1") (pintype "passive"))
      (node (ref "R10") (pin "2") (pinfunction "2_2") (pintype "passive"))
    )
    (net (code "49") (name "Net-(C19-Pad1)") (class "Default")
      (node (ref "C19") (pin "1") (pinfunction "1_1") (pintype "passive"))
      (node (ref "C30") (pin "1") (pinfunction "1_1") (pintype "passive"))
      (node (ref "R21") (pin "1") (pinfunction "1_1") (pintype "passive"))
      (node (ref "R22") (pin "2") (pinfunction "2_2") (pintype "passive"))
    )
    (net (code "50") (name "Net-(C19-Pad2)") (class "Default")
      (node (ref "C19") (pin "2") (pinfunction "2_2") (pintype "passive"))
      (node (ref "R19") (pin "1") (pinfunction "1_1") (pintype "passive"))
    )
    (net (code "51") (name "Net-(C20-Pad2)") (class "Default")
      (node (ref "C20") (pin "2") (pinfunction "2_2") (pintype "passive"))
      (node (ref "R18") (pin "1") (pinfunction "1_1") (pintype "passive"))
    )
    (net (code "52") (name "Net-(C24-Pad1)") (class "Default")
      (node (ref "C24") (pin "1") (pinfunction "1_1") (pintype "passive"))
      (node (ref "C37") (pin "1") (pinfunction "1_1") (pintype "passive"))
      (node (ref "R34") (pin "1") (pinfunction "1_1") (pintype "passive"))
      (node (ref "R35") (pin "2") (pinfunction "2_2") (pintype "passive"))
    )
    (net (code "53") (name "Net-(C24-Pad2)") (class "Default")
      (node (ref "C24") (pin "2") (pinfunction "2_2") (pintype "passive"))
      (node (ref "R32") (pin "1") (pinfunction "1_1") (pintype "passive"))
    )
    (net (code "54") (name "Net-(C26-Pad2)") (class "Default")
      (node (ref "C26") (pin "2") (pinfunction "2_2") (pintype "passive"))
      (node (ref "R31") (pin "1") (pinfunction "1_1") (pintype "passive"))
    )
    (net (code "55") (name "Net-(C29-Pad2)") (class "Default")
      (node (ref "C29") (pin "2") (pinfunction "2_2") (pintype "passive"))
      (node (ref "SJ2") (pin "2") (pinfunction "2_2") (pintype "passive"))
    )
    (net (code "56") (name "Net-(CHG-PadC)") (class "Default")
      (node (ref "CHG") (pin "C") (pinfunction "C_C") (pintype "passive"))
      (node (ref "R3") (pin "2") (pinfunction "2_2") (pintype "passive"))
    )
    (net (code "57") (name "Net-(D1-PadA)") (class "Default")
      (node (ref "D1") (pin "A") (pinfunction "A_A") (pintype "passive"))
      (node (ref "R1") (pin "1") (pinfunction "1_1") (pintype "passive"))
    )
    (net (code "58") (name "Net-(D2-PadA)") (class "Default")
      (node (ref "D2") (pin "A") (pinfunction "A_A") (pintype "passive"))
      (node (ref "R2") (pin "1") (pinfunction "1_1") (pintype "passive"))
    )
    (net (code "59") (name "Net-(FB1-P$1)") (class "Default")
      (node (ref "FB1") (pin "1") (pinfunction "P$1_1") (pintype "passive"))
      (node (ref "U6") (pin "5") (pinfunction "VO_P_5") (pintype "output"))
    )
    (net (code "60") (name "Net-(FB2-P$1)") (class "Default")
      (node (ref "FB2") (pin "1") (pinfunction "P$1_1") (pintype "passive"))
      (node (ref "U6") (pin "8") (pinfunction "VO_N_8") (pintype "output"))
    )
    (net (code "61") (name "Net-(FB5-P$1)") (class "Default")
      (node (ref "FB5") (pin "1") (pinfunction "P$1_1") (pintype "passive"))
      (node (ref "U8") (pin "5") (pinfunction "VO_P_5") (pintype "output"))
    )
    (net (code "62") (name "Net-(FB6-P$1)") (class "Default")
      (node (ref "FB6") (pin "1") (pinfunction "P$1_1") (pintype "passive"))
      (node (ref "U8") (pin "8") (pinfunction "VO_N_8") (pintype "output"))
    )
    (net (code "63") (name "Net-(J7-RXI)") (class "Default")
      (node (ref "J7") (pin "3") (pinfunction "RXI_3") (pintype "passive"))
      (node (ref "R29") (pin "1") (pinfunction "1_1") (pintype "passive"))
    )
    (net (code "64") (name "Net-(J7-TXO)") (class "Default")
      (node (ref "J7") (pin "2") (pinfunction "TXO_2") (pintype "passive"))
      (node (ref "R30") (pin "1") (pinfunction "1_1") (pintype "passive"))
    )
    (net (code "65") (name "Net-(Q3-D)") (class "Default")
      (node (ref "Q3") (pin "3") (pinfunction "D_3") (pintype "passive"))
      (node (ref "SW3") (pin "S") (pinfunction "S_S") (pintype "passive"))
    )
    (net (code "66") (name "Net-(U$45-CO)") (class "Default")
      (node (ref "U$45") (pin "CL_OUT") (pinfunction "CO_CL_OUT") (pintype "bidirectional"))
      (node (ref "U$51") (pin "C_IN") (pinfunction "CI_C_IN") (pintype "bidirectional"))
    )
    (net (code "67") (name "Net-(U$45-DO)") (class "Default")
      (node (ref "U$45") (pin "D_OUT") (pinfunction "DO_D_OUT") (pintype "bidirectional"))
      (node (ref "U$51") (pin "D_IN") (pinfunction "DI_D_IN") (pintype "bidirectional"))
    )
    (net (code "68") (name "Net-(U1-DCC)") (class "Default")
      (node (ref "L2") (pin "2") (pinfunction "2_2") (pintype "passive"))
      (node (ref "U1") (pin "10") (pinfunction "DCC_10") (pintype "bidirectional"))
    )
    (net (code "69") (name "Net-(U1-DEC4)") (class "Default")
      (node (ref "C4") (pin "1") (pinfunction "1_1") (pintype "passive"))
      (node (ref "L2") (pin "1") (pinfunction "1_1") (pintype "passive"))
      (node (ref "U1") (pin "9") (pinfunction "DEC4_9") (pintype "bidirectional"))
    )
    (net (code "70") (name "Net-(U1-P0.00{slash}XL1)") (class "Default")
      (node (ref "C1") (pin "1") (pinfunction "1_1") (pintype "passive"))
      (node (ref "U1") (pin "13") (pinfunction "P0.00/XL1_13") (pintype "bidirectional"))
      (node (ref "X4") (pin "P$1") (pinfunction "P$1_P$1") (pintype "bidirectional"))
    )
    (net (code "71") (name "Net-(U1-P0.01{slash}XL2)") (class "Default")
      (node (ref "C2") (pin "1") (pinfunction "1_1") (pintype "passive"))
      (node (ref "U1") (pin "14") (pinfunction "P0.01/XL2_14") (pintype "bidirectional"))
      (node (ref "X4") (pin "P$2") (pinfunction "P$2_P$2") (pintype "bidirectional"))
    )
    (net (code "72") (name "Net-(U3-PROG)") (class "Default")
      (node (ref "R7") (pin "2") (pinfunction "2_2") (pintype "passive"))
      (node (ref "U3") (pin "5") (pinfunction "PROG_5") (pintype "input"))
    )
    (net (code "73") (name "Net-(U3-STAT)") (class "Default")
      (node (ref "R3") (pin "1") (pinfunction "1_1") (pintype "passive"))
      (node (ref "U3") (pin "1") (pinfunction "STAT_1") (pintype "output"))
    )
    (net (code "74") (name "Net-(U4A-+IN)") (class "Default")
      (node (ref "C13") (pin "1") (pinfunction "1_1") (pintype "passive"))
      (node (ref "R8") (pin "2") (pinfunction "2_2") (pintype "passive"))
      (node (ref "R9") (pin "1") (pinfunction "1_1") (pintype "passive"))
      (node (ref "U4") (pin "3") (pinfunction "+IN_3") (pintype "input"))
    )
    (net (code "75") (name "Net-(U4B-+IN)") (class "Default")
      (node (ref "C14") (pin "2") (pinfunction "2_2") (pintype "passive"))
      (node (ref "R11") (pin "1") (pinfunction "1_1") (pintype "passive"))
      (node (ref "U4") (pin "10") (pinfunction "+IN_10") (pintype "input"))
    )
    (net (code "76") (name "Net-(U4B--IN)") (class "Default")
      (node (ref "R13") (pin "1") (pinfunction "1_1") (pintype "passive"))
      (node (ref "R14") (pin "1") (pinfunction "1_1") (pintype "passive"))
      (node (ref "U4") (pin "9") (pinfunction "-IN_9") (pintype "input"))
    )
    (net (code "77") (name "Net-(U4B-OUT)") (class "Default")
      (node (ref "R14") (pin "2") (pinfunction "2_2") (pintype "passive"))
      (node (ref "U4") (pin "5") (pinfunction "+IN_5") (pintype "input"))
      (node (ref "U4") (pin "8") (pinfunction "OUT_8") (pintype "output"))
    )
    (net (code "78") (name "Net-(U4C--IN)") (class "Default")
      (node (ref "R15") (pin "1") (pinfunction "1_1") (pintype "passive"))
      (node (ref "R16") (pin "1") (pinfunction "1_1") (pintype "passive"))
      (node (ref "U4") (pin "6") (pinfunction "-IN_6") (pintype "input"))
    )
    (net (code "79") (name "Net-(U4C-OUT)") (class "Default")
      (node (ref "JP3") (pin "1") (pinfunction "1_1") (pintype "passive"))
      (node (ref "R15") (pin "2") (pinfunction "2_2") (pintype "passive"))
      (node (ref "U4") (pin "7") (pinfunction "OUT_7") (pintype "output"))
    )
    (net (code "80") (name "Net-(U6-IN_N)") (class "Default")
      (node (ref "R18") (pin "2") (pinfunction "2_2") (pintype "passive"))
      (node (ref "U6") (pin "4") (pinfunction "IN_N_4") (pintype "input"))
    )
    (net (code "81") (name "Net-(U6-IN_P)") (class "Default")
      (node (ref "R19") (pin "2") (pinfunction "2_2") (pintype "passive"))
      (node (ref "U6") (pin "3") (pinfunction "IN_P_3") (pintype "input"))
    )
    (net (code "82") (name "Net-(U8-IN_N)") (class "Default")
      (node (ref "R31") (pin "2") (pinfunction "2_2") (pintype "passive"))
      (node (ref "U8") (pin "4") (pinfunction "IN_N_4") (pintype "input"))
    )
    (net (code "83") (name "Net-(U8-IN_P)") (class "Default")
      (node (ref "R32") (pin "2") (pinfunction "2_2") (pintype "passive"))
      (node (ref "U8") (pin "3") (pinfunction "IN_P_3") (pintype "input"))
    )
    (net (code "84") (name "VBAT") (class "Default")
      (node (ref "C5") (pin "1") (pinfunction "1_1") (pintype "passive"))
      (node (ref "R4") (pin "1") (pinfunction "1_1") (pintype "passive"))
      (node (ref "SW3") (pin "P") (pinfunction "P_P") (pintype "passive"))
      (node (ref "U3") (pin "3") (pinfunction "VBAT_3") (pintype "power_in"))
      (node (ref "X2") (pin "2") (pinfunction "2_2") (pintype "passive"))
    )
    (net (code "85") (name "VBUS") (class "Default")
      (node (ref "CHG") (pin "A") (pinfunction "A_A") (pintype "passive"))
      (node (ref "D5") (pin "A") (pinfunction "A_A") (pintype "passive"))
      (node (ref "J7") (pin "4") (pinfunction "VCC_4") (pintype "passive"))
      (node (ref "Q3") (pin "1") (pinfunction "G_1") (pintype "passive"))
      (node (ref "R12") (pin "1") (pinfunction "1_1") (pintype "passive"))
      (node (ref "U3") (pin "4") (pinfunction "VDD_4") (pintype "power_in"))
      (node (ref "X3") (pin "VBUS") (pinfunction "VBUS_VBUS") (pintype "power_in"))
    )
    (net (code "86") (name "VCCA") (class "Default")
      (node (ref "C11") (pin "1") (pinfunction "1_1") (pintype "passive"))
      (node (ref "L1") (pin "2") (pinfunction "2_2") (pintype "passive"))
      (node (ref "R10") (pin "1") (pinfunction "1_1") (pintype "passive"))
      (node (ref "R8") (pin "1") (pinfunction "1_1") (pintype "passive"))
      (node (ref "U4") (pin "4") (pinfunction "P$V+_4") (pintype "bidirectional"))
    )
    (net (code "87") (name "VCC_2") (class "Default")
      (node (ref "C16") (pin "1") (pinfunction "1_1") (pintype "passive"))
      (node (ref "C17") (pin "1") (pinfunction "1_1") (pintype "passive"))
      (node (ref "C18") (pin "1") (pinfunction "1_1") (pintype "passive"))
      (node (ref "C21") (pin "1") (pinfunction "1_1") (pintype "passive"))
      (node (ref "C25") (pin "1") (pinfunction "1_1") (pintype "passive"))
      (node (ref "R20") (pin "2") (pinfunction "2_2") (pintype "passive"))
      (node (ref "R24") (pin "2") (pinfunction "2_2") (pintype "passive"))
      (node (ref "U$45") (pin "V_CC") (pinfunction "VCC_V_CC") (pintype "bidirectional"))
      (node (ref "U$51") (pin "V_CC") (pinfunction "VCC_V_CC") (pintype "bidirectional"))
      (node (ref "U5") (pin "5") (pinfunction "OUT_5") (pintype "power_in"))
      (node (ref "U6") (pin "6") (pinfunction "VDD_6") (pintype "power_in"))
      (node (ref "U8") (pin "6") (pinfunction "VDD_6") (pintype "power_in"))
    )
    (net (code "88") (name "unconnected-(J4-Pad1)") (class "Default")
      (node (ref "J4") (pin "1") (pinfunction "1_1") (pintype "passive"))
    )
    (net (code "89") (name "unconnected-(J4-Pad2)") (class "Default")
      (node (ref "J4") (pin "2") (pinfunction "2_2") (pintype "passive"))
    )
    (net (code "90") (name "unconnected-(J4-Pad3)") (class "Default")
      (node (ref "J4") (pin "3") (pinfunction "3_3") (pintype "passive"))
    )
    (net (code "91") (name "unconnected-(J4-Pad4)") (class "Default")
      (node (ref "J4") (pin "4") (pinfunction "4_4") (pintype "passive"))
    )
    (net (code "92") (name "unconnected-(J4-Pad5)") (class "Default")
      (node (ref "J4") (pin "5") (pinfunction "5_5") (pintype "passive"))
    )
    (net (code "93") (name "unconnected-(J4-Pad6)") (class "Default")
      (node (ref "J4") (pin "6") (pinfunction "6_6") (pintype "passive"))
    )
    (net (code "94") (name "unconnected-(J4-Pad7)") (class "Default")
      (node (ref "J4") (pin "7") (pinfunction "7_7") (pintype "passive"))
    )
    (net (code "95") (name "unconnected-(J7-CTS-Pad5)") (class "Default")
      (node (ref "J7") (pin "5") (pinfunction "CTS_5") (pintype "passive"))
    )
    (net (code "96") (name "unconnected-(J10-Pad1)") (class "Default")
      (node (ref "J10") (pin "1") (pinfunction "1_1") (pintype "passive"))
    )
    (net (code "97") (name "unconnected-(J10-Pad2)") (class "Default")
      (node (ref "J10") (pin "2") (pinfunction "2_2") (pintype "passive"))
    )
    (net (code "98") (name "unconnected-(J10-Pad3)") (class "Default")
      (node (ref "J10") (pin "3") (pinfunction "3_3") (pintype "passive"))
    )
    (net (code "99") (name "unconnected-(J10-Pad4)") (class "Default")
      (node (ref "J10") (pin "4") (pinfunction "4_4") (pintype "passive"))
    )
    (net (code "100") (name "unconnected-(J10-Pad5)") (class "Default")
      (node (ref "J10") (pin "5") (pinfunction "5_5") (pintype "passive"))
    )
    (net (code "101") (name "unconnected-(J10-Pad6)") (class "Default")
      (node (ref "J10") (pin "6") (pinfunction "6_6") (pintype "passive"))
    )
    (net (code "102") (name "unconnected-(J10-Pad7)") (class "Default")
      (node (ref "J10") (pin "7") (pinfunction "7_7") (pintype "passive"))
    )
    (net (code "103") (name "unconnected-(J11-Pad1)") (class "Default")
      (node (ref "J11") (pin "1") (pinfunction "1_1") (pintype "passive"))
    )
    (net (code "104") (name "unconnected-(J11-Pad2)") (class "Default")
      (node (ref "J11") (pin "2") (pinfunction "2_2") (pintype "passive"))
    )
    (net (code "105") (name "unconnected-(J11-Pad3)") (class "Default")
      (node (ref "J11") (pin "3") (pinfunction "3_3") (pintype "passive"))
    )
    (net (code "106") (name "unconnected-(J11-Pad4)") (class "Default")
      (node (ref "J11") (pin "4") (pinfunction "4_4") (pintype "passive"))
    )
    (net (code "107") (name "unconnected-(J11-Pad5)") (class "Default")
      (node (ref "J11") (pin "5") (pinfunction "5_5") (pintype "passive"))
    )
    (net (code "108") (name "unconnected-(J11-Pad6)") (class "Default")
      (node (ref "J11") (pin "6") (pinfunction "6_6") (pintype "passive"))
    )
    (net (code "109") (name "unconnected-(J11-Pad7)") (class "Default")
      (node (ref "J11") (pin "7") (pinfunction "7_7") (pintype "passive"))
    )
    (net (code "110") (name "unconnected-(J12-Pad1)") (class "Default")
      (node (ref "J12") (pin "1") (pinfunction "1_1") (pintype "passive"))
    )
    (net (code "111") (name "unconnected-(J12-Pad2)") (class "Default")
      (node (ref "J12") (pin "2") (pinfunction "2_2") (pintype "passive"))
    )
    (net (code "112") (name "unconnected-(J12-Pad3)") (class "Default")
      (node (ref "J12") (pin "3") (pinfunction "3_3") (pintype "passive"))
    )
    (net (code "113") (name "unconnected-(J12-Pad4)") (class "Default")
      (node (ref "J12") (pin "4") (pinfunction "4_4") (pintype "passive"))
    )
    (net (code "114") (name "unconnected-(J12-Pad5)") (class "Default")
      (node (ref "J12") (pin "5") (pinfunction "5_5") (pintype "passive"))
    )
    (net (code "115") (name "unconnected-(J12-Pad6)") (class "Default")
      (node (ref "J12") (pin "6") (pinfunction "6_6") (pintype "passive"))
    )
    (net (code "116") (name "unconnected-(J12-Pad7)") (class "Default")
      (node (ref "J12") (pin "7") (pinfunction "7_7") (pintype "passive"))
    )
    (net (code "117") (name "unconnected-(J13-Pad1)") (class "Default")
      (node (ref "J13") (pin "1") (pinfunction "1_1") (pintype "passive"))
    )
    (net (code "118") (name "unconnected-(J13-Pad2)") (class "Default")
      (node (ref "J13") (pin "2") (pinfunction "2_2") (pintype "passive"))
    )
    (net (code "119") (name "unconnected-(J13-Pad3)") (class "Default")
      (node (ref "J13") (pin "3") (pinfunction "3_3") (pintype "passive"))
    )
    (net (code "120") (name "unconnected-(J13-Pad4)") (class "Default")
      (node (ref "J13") (pin "4") (pinfunction "4_4") (pintype "passive"))
    )
    (net (code "121") (name "unconnected-(J13-Pad5)") (class "Default")
      (node (ref "J13") (pin "5") (pinfunction "5_5") (pintype "passive"))
    )
    (net (code "122") (name "unconnected-(J13-Pad6)") (class "Default")
      (node (ref "J13") (pin "6") (pinfunction "6_6") (pintype "passive"))
    )
    (net (code "123") (name "unconnected-(J13-Pad7)") (class "Default")
      (node (ref "J13") (pin "7") (pinfunction "7_7") (pintype "passive"))
    )
    (net (code "124") (name "unconnected-(J14-Pad1)") (class "Default")
      (node (ref "J14") (pin "1") (pinfunction "1_1") (pintype "passive"))
    )
    (net (code "125") (name "unconnected-(J14-Pad2)") (class "Default")
      (node (ref "J14") (pin "2") (pinfunction "2_2") (pintype "passive"))
    )
    (net (code "126") (name "unconnected-(J14-Pad3)") (class "Default")
      (node (ref "J14") (pin "3") (pinfunction "3_3") (pintype "passive"))
    )
    (net (code "127") (name "unconnected-(J14-Pad4)") (class "Default")
      (node (ref "J14") (pin "4") (pinfunction "4_4") (pintype "passive"))
    )
    (net (code "128") (name "unconnected-(J14-Pad5)") (class "Default")
      (node (ref "J14") (pin "5") (pinfunction "5_5") (pintype "passive"))
    )
    (net (code "129") (name "unconnected-(J14-Pad6)") (class "Default")
      (node (ref "J14") (pin "6") (pinfunction "6_6") (pintype "passive"))
    )
    (net (code "130") (name "unconnected-(J14-Pad7)") (class "Default")
      (node (ref "J14") (pin "7") (pinfunction "7_7") (pintype "passive"))
    )
    (net (code "131") (name "unconnected-(J15-Pad1)") (class "Default")
      (node (ref "J15") (pin "1") (pinfunction "1_1") (pintype "passive"))
    )
    (net (code "132") (name "unconnected-(J15-Pad2)") (class "Default")
      (node (ref "J15") (pin "2") (pinfunction "2_2") (pintype "passive"))
    )
    (net (code "133") (name "unconnected-(J15-Pad3)") (class "Default")
      (node (ref "J15") (pin "3") (pinfunction "3_3") (pintype "passive"))
    )
    (net (code "134") (name "unconnected-(J15-Pad4)") (class "Default")
      (node (ref "J15") (pin "4") (pinfunction "4_4") (pintype "passive"))
    )
    (net (code "135") (name "unconnected-(J15-Pad5)") (class "Default")
      (node (ref "J15") (pin "5") (pinfunction "5_5") (pintype "passive"))
    )
    (net (code "136") (name "unconnected-(J15-Pad6)") (class "Default")
      (node (ref "J15") (pin "6") (pinfunction "6_6") (pintype "passive"))
    )
    (net (code "137") (name "unconnected-(J15-Pad7)") (class "Default")
      (node (ref "J15") (pin "7") (pinfunction "7_7") (pintype "passive"))
    )
    (net (code "138") (name "unconnected-(SW3-PadO)") (class "Default")
      (node (ref "SW3") (pin "O") (pinfunction "O_O") (pintype "passive"))
    )
    (net (code "139") (name "unconnected-(U$51-CO-PadCL_OUT)") (class "Default")
      (node (ref "U$51") (pin "CL_OUT") (pinfunction "CO_CL_OUT") (pintype "bidirectional"))
    )
    (net (code "140") (name "unconnected-(U$51-DO-PadD_OUT)") (class "Default")
      (node (ref "U$51") (pin "D_OUT") (pinfunction "DO_D_OUT") (pintype "bidirectional"))
    )
    (net (code "141") (name "unconnected-(U1-P0.23-Pad41)") (class "Default")
      (node (ref "U1") (pin "41") (pinfunction "P0.23_41") (pintype "bidirectional"))
    )
    (net (code "142") (name "unconnected-(U1-P0.24-Pad40)") (class "Default")
      (node (ref "U1") (pin "40") (pinfunction "P0.24_40") (pintype "bidirectional"))
    )
    (net (code "143") (name "unconnected-(U2-P4-Pad4)") (class "Default")
      (node (ref "U2") (pin "4") (pinfunction "P4_4") (pintype "bidirectional"))
    )
    (net (code "144") (name "unconnected-(U4D-+IN-Pad12)") (class "Default")
      (node (ref "U4") (pin "12") (pinfunction "+IN_12") (pintype "input"))
    )
    (net (code "145") (name "unconnected-(U4D--IN-Pad13)") (class "Default")
      (node (ref "U4") (pin "13") (pinfunction "-IN_13") (pintype "input"))
    )
    (net (code "146") (name "unconnected-(U4D-OUT-Pad14)") (class "Default")
      (node (ref "U4") (pin "14") (pinfunction "OUT_14") (pintype "output"))
    )
    (net (code "147") (name "unconnected-(U5-P4-Pad4)") (class "Default")
      (node (ref "U5") (pin "4") (pinfunction "P4_4") (pintype "bidirectional"))
    )
    (net (code "148") (name "unconnected-(U6-NC-Pad2)") (class "Default")
      (node (ref "U6") (pin "2") (pinfunction "NC_2") (pintype "no_connect"))
    )
    (net (code "149") (name "unconnected-(U8-NC-Pad2)") (class "Default")
      (node (ref "U8") (pin "2") (pinfunction "NC_2") (pintype "no_connect"))
    )
    (net (code "150") (name "unconnected-(X3-PadID)") (class "Default")
      (node (ref "X3") (pin "ID") (pinfunction "ID_ID") (pintype "bidirectional"))
    )
  )
)
